# mSD-Shield-Mega_v11.net
KiCad netlist of a schematic drawn in EAGLE
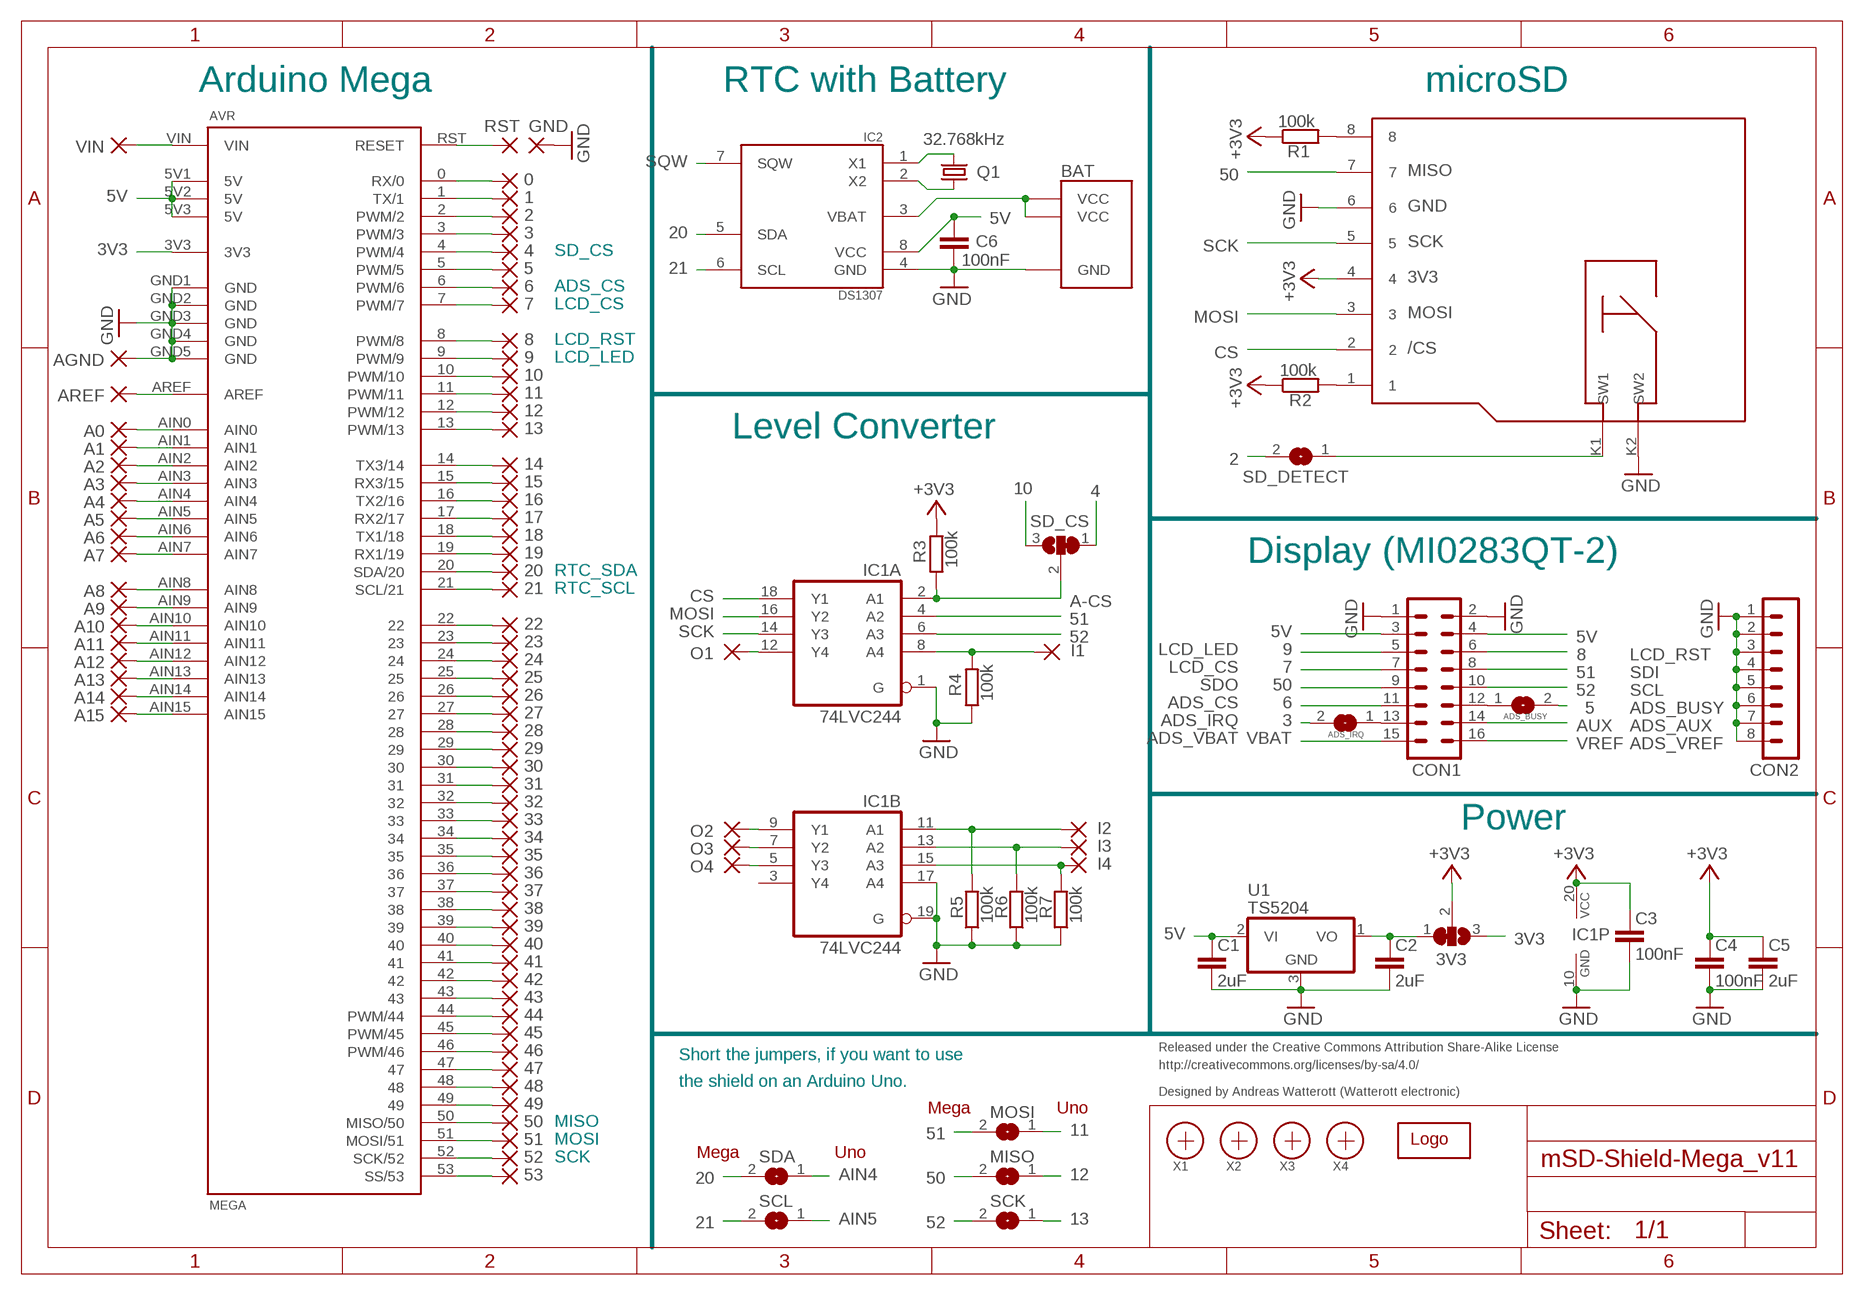
[diagram p0: schematic, sheet 1]

(export (version "E")
  (design (tool "Eeschema 10.0.6"))
  (components
    (comp (ref "0")
      (value "1,6/0,8")
      (footprint "eagle-import:1,6_0,8")
      (libsource (lib "eagle-import") (part "1,6/0,8"))
    )
    (comp (ref "1")
      (value "1,6/0,8")
      (footprint "eagle-import:1,6_0,8")
      (libsource (lib "eagle-import") (part "1,6/0,8"))
    )
    (comp (ref "2")
      (value "1,6/0,8")
      (footprint "eagle-import:1,6_0,8")
      (libsource (lib "eagle-import") (part "1,6/0,8"))
    )
    (comp (ref "3")
      (value "1,6/0,8")
      (footprint "eagle-import:1,6_0,8")
      (libsource (lib "eagle-import") (part "1,6/0,8"))
    )
    (comp (ref "3V3")
      (value "SJ2W")
      (footprint "eagle-import:SJ_2")
      (libsource (lib "eagle-import") (part "SJ2W"))
    )
    (comp (ref "4")
      (value "1,6/0,8")
      (footprint "eagle-import:1,6_0,8")
      (libsource (lib "eagle-import") (part "1,6/0,8"))
    )
    (comp (ref "5")
      (value "1,6/0,8")
      (footprint "eagle-import:1,6_0,8")
      (libsource (lib "eagle-import") (part "1,6/0,8"))
    )
    (comp (ref "6")
      (value "1,6/0,8")
      (footprint "eagle-import:1,6_0,8")
      (libsource (lib "eagle-import") (part "1,6/0,8"))
    )
    (comp (ref "7")
      (value "1,6/0,8")
      (footprint "eagle-import:1,6_0,8")
      (libsource (lib "eagle-import") (part "1,6/0,8"))
    )
    (comp (ref "8")
      (value "1,6/0,8")
      (footprint "eagle-import:1,6_0,8")
      (libsource (lib "eagle-import") (part "1,6/0,8"))
    )
    (comp (ref "9")
      (value "1,6/0,8")
      (footprint "eagle-import:1,6_0,8")
      (libsource (lib "eagle-import") (part "1,6/0,8"))
    )
    (comp (ref "10")
      (value "1,6/0,8")
      (footprint "eagle-import:1,6_0,8")
      (libsource (lib "eagle-import") (part "1,6/0,8"))
    )
    (comp (ref "11")
      (value "1,6/0,8")
      (footprint "eagle-import:1,6_0,8")
      (libsource (lib "eagle-import") (part "1,6/0,8"))
    )
    (comp (ref "12")
      (value "1,6/0,8")
      (footprint "eagle-import:1,6_0,8")
      (libsource (lib "eagle-import") (part "1,6/0,8"))
    )
    (comp (ref "13")
      (value "1,6/0,8")
      (footprint "eagle-import:1,6_0,8")
      (libsource (lib "eagle-import") (part "1,6/0,8"))
    )
    (comp (ref "14")
      (value "1,6/0,8")
      (footprint "eagle-import:1,6_0,8")
      (libsource (lib "eagle-import") (part "1,6/0,8"))
    )
    (comp (ref "15")
      (value "1,6/0,8")
      (footprint "eagle-import:1,6_0,8")
      (libsource (lib "eagle-import") (part "1,6/0,8"))
    )
    (comp (ref "16")
      (value "1,6/0,8")
      (footprint "eagle-import:1,6_0,8")
      (libsource (lib "eagle-import") (part "1,6/0,8"))
    )
    (comp (ref "17")
      (value "1,6/0,8")
      (footprint "eagle-import:1,6_0,8")
      (libsource (lib "eagle-import") (part "1,6/0,8"))
    )
    (comp (ref "18")
      (value "1,6/0,8")
      (footprint "eagle-import:1,6_0,8")
      (libsource (lib "eagle-import") (part "1,6/0,8"))
    )
    (comp (ref "19")
      (value "1,6/0,8")
      (footprint "eagle-import:1,6_0,8")
      (libsource (lib "eagle-import") (part "1,6/0,8"))
    )
    (comp (ref "20")
      (value "1,6/0,8")
      (footprint "eagle-import:1,6_0,8")
      (libsource (lib "eagle-import") (part "1,6/0,8"))
    )
    (comp (ref "21")
      (value "1,6/0,8")
      (footprint "eagle-import:1,6_0,8")
      (libsource (lib "eagle-import") (part "1,6/0,8"))
    )
    (comp (ref "22")
      (value "1,6/0,8")
      (footprint "eagle-import:1,6_0,8")
      (libsource (lib "eagle-import") (part "1,6/0,8"))
    )
    (comp (ref "23")
      (value "1,6/0,8")
      (footprint "eagle-import:1,6_0,8")
      (libsource (lib "eagle-import") (part "1,6/0,8"))
    )
    (comp (ref "24")
      (value "1,6/0,8")
      (footprint "eagle-import:1,6_0,8")
      (libsource (lib "eagle-import") (part "1,6/0,8"))
    )
    (comp (ref "25")
      (value "1,6/0,8")
      (footprint "eagle-import:1,6_0,8")
      (libsource (lib "eagle-import") (part "1,6/0,8"))
    )
    (comp (ref "26")
      (value "1,6/0,8")
      (footprint "eagle-import:1,6_0,8")
      (libsource (lib "eagle-import") (part "1,6/0,8"))
    )
    (comp (ref "27")
      (value "1,6/0,8")
      (footprint "eagle-import:1,6_0,8")
      (libsource (lib "eagle-import") (part "1,6/0,8"))
    )
    (comp (ref "28")
      (value "1,6/0,8")
      (footprint "eagle-import:1,6_0,8")
      (libsource (lib "eagle-import") (part "1,6/0,8"))
    )
    (comp (ref "29")
      (value "1,6/0,8")
      (footprint "eagle-import:1,6_0,8")
      (libsource (lib "eagle-import") (part "1,6/0,8"))
    )
    (comp (ref "30")
      (value "1,6/0,8")
      (footprint "eagle-import:1,6_0,8")
      (libsource (lib "eagle-import") (part "1,6/0,8"))
    )
    (comp (ref "31")
      (value "1,6/0,8")
      (footprint "eagle-import:1,6_0,8")
      (libsource (lib "eagle-import") (part "1,6/0,8"))
    )
    (comp (ref "32")
      (value "1,6/0,8")
      (footprint "eagle-import:1,6_0,8")
      (libsource (lib "eagle-import") (part "1,6/0,8"))
    )
    (comp (ref "33")
      (value "1,6/0,8")
      (footprint "eagle-import:1,6_0,8")
      (libsource (lib "eagle-import") (part "1,6/0,8"))
    )
    (comp (ref "34")
      (value "1,6/0,8")
      (footprint "eagle-import:1,6_0,8")
      (libsource (lib "eagle-import") (part "1,6/0,8"))
    )
    (comp (ref "35")
      (value "1,6/0,8")
      (footprint "eagle-import:1,6_0,8")
      (libsource (lib "eagle-import") (part "1,6/0,8"))
    )
    (comp (ref "36")
      (value "1,6/0,8")
      (footprint "eagle-import:1,6_0,8")
      (libsource (lib "eagle-import") (part "1,6/0,8"))
    )
    (comp (ref "37")
      (value "1,6/0,8")
      (footprint "eagle-import:1,6_0,8")
      (libsource (lib "eagle-import") (part "1,6/0,8"))
    )
    (comp (ref "38")
      (value "1,6/0,8")
      (footprint "eagle-import:1,6_0,8")
      (libsource (lib "eagle-import") (part "1,6/0,8"))
    )
    (comp (ref "39")
      (value "1,6/0,8")
      (footprint "eagle-import:1,6_0,8")
      (libsource (lib "eagle-import") (part "1,6/0,8"))
    )
    (comp (ref "40")
      (value "1,6/0,8")
      (footprint "eagle-import:1,6_0,8")
      (libsource (lib "eagle-import") (part "1,6/0,8"))
    )
    (comp (ref "41")
      (value "1,6/0,8")
      (footprint "eagle-import:1,6_0,8")
      (libsource (lib "eagle-import") (part "1,6/0,8"))
    )
    (comp (ref "42")
      (value "1,6/0,8")
      (footprint "eagle-import:1,6_0,8")
      (libsource (lib "eagle-import") (part "1,6/0,8"))
    )
    (comp (ref "43")
      (value "1,6/0,8")
      (footprint "eagle-import:1,6_0,8")
      (libsource (lib "eagle-import") (part "1,6/0,8"))
    )
    (comp (ref "44")
      (value "1,6/0,8")
      (footprint "eagle-import:1,6_0,8")
      (libsource (lib "eagle-import") (part "1,6/0,8"))
    )
    (comp (ref "45")
      (value "1,6/0,8")
      (footprint "eagle-import:1,6_0,8")
      (libsource (lib "eagle-import") (part "1,6/0,8"))
    )
    (comp (ref "46")
      (value "1,6/0,8")
      (footprint "eagle-import:1,6_0,8")
      (libsource (lib "eagle-import") (part "1,6/0,8"))
    )
    (comp (ref "47")
      (value "1,6/0,8")
      (footprint "eagle-import:1,6_0,8")
      (libsource (lib "eagle-import") (part "1,6/0,8"))
    )
    (comp (ref "48")
      (value "1,6/0,8")
      (footprint "eagle-import:1,6_0,8")
      (libsource (lib "eagle-import") (part "1,6/0,8"))
    )
    (comp (ref "49")
      (value "1,6/0,8")
      (footprint "eagle-import:1,6_0,8")
      (libsource (lib "eagle-import") (part "1,6/0,8"))
    )
    (comp (ref "50")
      (value "1,6/0,8")
      (footprint "eagle-import:1,6_0,8")
      (libsource (lib "eagle-import") (part "1,6/0,8"))
    )
    (comp (ref "51")
      (value "1,6/0,8")
      (footprint "eagle-import:1,6_0,8")
      (libsource (lib "eagle-import") (part "1,6/0,8"))
    )
    (comp (ref "52")
      (value "1,6/0,8")
      (footprint "eagle-import:1,6_0,8")
      (libsource (lib "eagle-import") (part "1,6/0,8"))
    )
    (comp (ref "53")
      (value "1,6/0,8")
      (footprint "eagle-import:1,6_0,8")
      (libsource (lib "eagle-import") (part "1,6/0,8"))
    )
    (comp (ref "A0")
      (value "1,6/0,8")
      (footprint "eagle-import:1,6_0,8")
      (libsource (lib "eagle-import") (part "1,6/0,8"))
    )
    (comp (ref "A1")
      (value "1,6/0,8")
      (footprint "eagle-import:1,6_0,8")
      (libsource (lib "eagle-import") (part "1,6/0,8"))
    )
    (comp (ref "A2")
      (value "1,6/0,8")
      (footprint "eagle-import:1,6_0,8")
      (libsource (lib "eagle-import") (part "1,6/0,8"))
    )
    (comp (ref "A3")
      (value "1,6/0,8")
      (footprint "eagle-import:1,6_0,8")
      (libsource (lib "eagle-import") (part "1,6/0,8"))
    )
    (comp (ref "A4")
      (value "1,6/0,8")
      (footprint "eagle-import:1,6_0,8")
      (libsource (lib "eagle-import") (part "1,6/0,8"))
    )
    (comp (ref "A5")
      (value "1,6/0,8")
      (footprint "eagle-import:1,6_0,8")
      (libsource (lib "eagle-import") (part "1,6/0,8"))
    )
    (comp (ref "A6")
      (value "1,6/0,8")
      (footprint "eagle-import:1,6_0,8")
      (libsource (lib "eagle-import") (part "1,6/0,8"))
    )
    (comp (ref "A7")
      (value "1,6/0,8")
      (footprint "eagle-import:1,6_0,8")
      (libsource (lib "eagle-import") (part "1,6/0,8"))
    )
    (comp (ref "A8")
      (value "1,6/0,8")
      (footprint "eagle-import:1,6_0,8")
      (libsource (lib "eagle-import") (part "1,6/0,8"))
    )
    (comp (ref "A9")
      (value "1,6/0,8")
      (footprint "eagle-import:1,6_0,8")
      (libsource (lib "eagle-import") (part "1,6/0,8"))
    )
    (comp (ref "A10")
      (value "1,6/0,8")
      (footprint "eagle-import:1,6_0,8")
      (libsource (lib "eagle-import") (part "1,6/0,8"))
    )
    (comp (ref "A11")
      (value "1,6/0,8")
      (footprint "eagle-import:1,6_0,8")
      (libsource (lib "eagle-import") (part "1,6/0,8"))
    )
    (comp (ref "A12")
      (value "1,6/0,8")
      (footprint "eagle-import:1,6_0,8")
      (libsource (lib "eagle-import") (part "1,6/0,8"))
    )
    (comp (ref "A13")
      (value "1,6/0,8")
      (footprint "eagle-import:1,6_0,8")
      (libsource (lib "eagle-import") (part "1,6/0,8"))
    )
    (comp (ref "A14")
      (value "1,6/0,8")
      (footprint "eagle-import:1,6_0,8")
      (libsource (lib "eagle-import") (part "1,6/0,8"))
    )
    (comp (ref "A15")
      (value "1,6/0,8")
      (footprint "eagle-import:1,6_0,8")
      (libsource (lib "eagle-import") (part "1,6/0,8"))
    )
    (comp (ref "ADS_BUSY")
      (value "SJ")
      (footprint "eagle-import:SJ")
      (libsource (lib "eagle-import") (part "SJ"))
    )
    (comp (ref "ADS_IRQ")
      (value "SJ")
      (footprint "eagle-import:SJ")
      (libsource (lib "eagle-import") (part "SJ"))
    )
    (comp (ref "AGND")
      (value "1,6/0,8")
      (footprint "eagle-import:1,6_0,8")
      (libsource (lib "eagle-import") (part "1,6/0,8"))
    )
    (comp (ref "AREF")
      (value "1,6/0,8")
      (footprint "eagle-import:1,6_0,8")
      (libsource (lib "eagle-import") (part "1,6/0,8"))
    )
    (comp (ref "AVR")
      (value "MEGA")
      (footprint "eagle-import:MEGA")
      (libsource (lib "eagle-import") (part "MEGA"))
    )
    (comp (ref "BAT")
      (value "CR2032")
      (footprint "eagle-import:KC3002S")
      (libsource (lib "eagle-import") (part "KC3002S"))
    )
    (comp (ref "C1")
      (value "2uF")
      (footprint "eagle-import:C0805")
      (libsource (lib "eagle-import") (part "C-EUC0805"))
    )
    (comp (ref "C2")
      (value "2uF")
      (footprint "eagle-import:C0805")
      (libsource (lib "eagle-import") (part "C-EUC0805"))
    )
    (comp (ref "C3")
      (value "100nF")
      (footprint "eagle-import:C0603")
      (libsource (lib "eagle-import") (part "C-EUC0603"))
    )
    (comp (ref "C4")
      (value "100nF")
      (footprint "eagle-import:C0603")
      (libsource (lib "eagle-import") (part "C-EUC0603"))
    )
    (comp (ref "C5")
      (value "2uF")
      (footprint "eagle-import:C0603")
      (libsource (lib "eagle-import") (part "C-EUC0603"))
    )
    (comp (ref "C6")
      (value "100nF")
      (footprint "eagle-import:C0603")
      (libsource (lib "eagle-import") (part "C-EUC0603"))
    )
    (comp (ref "CON1")
      (value "MA08-2")
      (footprint "eagle-import:MA08-2")
      (libsource (lib "eagle-import") (part "MA08-2"))
    )
    (comp (ref "CON2")
      (value "MA08-1")
      (footprint "eagle-import:MA08-1")
      (libsource (lib "eagle-import") (part "MA08-1"))
    )
    (comp (ref "GND")
      (value "SMD2")
      (footprint "eagle-import:SMD1,27-2,54")
      (libsource (lib "eagle-import") (part "SMD2"))
    )
    (comp (ref "I1")
      (value "SMD2")
      (footprint "eagle-import:SMD1,27-2,54")
      (libsource (lib "eagle-import") (part "SMD2"))
    )
    (comp (ref "I2")
      (value "SMD2")
      (footprint "eagle-import:SMD1,27-2,54")
      (libsource (lib "eagle-import") (part "SMD2"))
    )
    (comp (ref "I3")
      (value "SMD2")
      (footprint "eagle-import:SMD1,27-2,54")
      (libsource (lib "eagle-import") (part "SMD2"))
    )
    (comp (ref "I4")
      (value "SMD2")
      (footprint "eagle-import:SMD1,27-2,54")
      (libsource (lib "eagle-import") (part "SMD2"))
    )
    (comp (ref "IC1")
      (value "74LVC244")
      (footprint "eagle-import:SO20W")
      (libsource (lib "eagle-import") (part "74244DWHC"))
    )
    (comp (ref "IC2")
      (value "DS1307")
      (footprint "eagle-import:SO8")
      (libsource (lib "eagle-import") (part "DS1307"))
    )
    (comp (ref "MISO")
      (value "SJ")
      (footprint "eagle-import:SJ")
      (libsource (lib "eagle-import") (part "SJ"))
    )
    (comp (ref "MOSI")
      (value "SJ")
      (footprint "eagle-import:SJ")
      (libsource (lib "eagle-import") (part "SJ"))
    )
    (comp (ref "O1")
      (value "SMD2")
      (footprint "eagle-import:SMD1,27-2,54")
      (libsource (lib "eagle-import") (part "SMD2"))
    )
    (comp (ref "O2")
      (value "SMD2")
      (footprint "eagle-import:SMD1,27-2,54")
      (libsource (lib "eagle-import") (part "SMD2"))
    )
    (comp (ref "O3")
      (value "SMD2")
      (footprint "eagle-import:SMD1,27-2,54")
      (libsource (lib "eagle-import") (part "SMD2"))
    )
    (comp (ref "O4")
      (value "SMD2")
      (footprint "eagle-import:SMD1,27-2,54")
      (libsource (lib "eagle-import") (part "SMD2"))
    )
    (comp (ref "Q1")
      (value "32.768kHz")
      (footprint "eagle-import:TC26V")
      (libsource (lib "eagle-import") (part "CRYSTALTC26V"))
    )
    (comp (ref "R1")
      (value "100k")
      (footprint "eagle-import:R0603")
      (libsource (lib "eagle-import") (part "R-EU_R0603"))
    )
    (comp (ref "R2")
      (value "100k")
      (footprint "eagle-import:R0603")
      (libsource (lib "eagle-import") (part "R-EU_R0603"))
    )
    (comp (ref "R3")
      (value "100k")
      (footprint "eagle-import:R0603")
      (libsource (lib "eagle-import") (part "R-EU_R0603"))
    )
    (comp (ref "R4")
      (value "100k")
      (footprint "eagle-import:R0603")
      (libsource (lib "eagle-import") (part "R-EU_R0603"))
    )
    (comp (ref "R5")
      (value "100k")
      (footprint "eagle-import:R0603")
      (libsource (lib "eagle-import") (part "R-EU_R0603"))
    )
    (comp (ref "R6")
      (value "100k")
      (footprint "eagle-import:R0603")
      (libsource (lib "eagle-import") (part "R-EU_R0603"))
    )
    (comp (ref "R7")
      (value "100k")
      (footprint "eagle-import:R0603")
      (libsource (lib "eagle-import") (part "R-EU_R0603"))
    )
    (comp (ref "RST")
      (value "SMD2")
      (footprint "eagle-import:SMD1,27-2,54")
      (libsource (lib "eagle-import") (part "SMD2"))
    )
    (comp (ref "SCK") (value "SJ") (footprint "eagle-import:SJ") (libsource (lib "eagle-import") (part "SJ")))
    (comp (ref "SCL") (value "SJ") (footprint "eagle-import:SJ") (libsource (lib "eagle-import") (part "SJ")))
    (comp (ref "SDA") (value "SJ") (footprint "eagle-import:SJ") (libsource (lib "eagle-import") (part "SJ")))
    (comp (ref "SD_CS")
      (value "SJ2W")
      (footprint "eagle-import:SJ_2")
      (libsource (lib "eagle-import") (part "SJ2W"))
    )
    (comp (ref "SD_DETECT")
      (value "SJ")
      (footprint "eagle-import:SJ")
      (libsource (lib "eagle-import") (part "SJ"))
    )
    (comp (ref "U$1")
      (value "WE-LOGO")
      (footprint "eagle-import:WE-LOGO")
      (libsource (lib "eagle-import") (part "WE-LOGO"))
    )
    (comp (ref "U1")
      (value "TS5204")
      (footprint "eagle-import:SOT23")
      (libsource (lib "eagle-import") (part "TS5204"))
    )
    (comp (ref "VIN")
      (value "1,6/0,8")
      (footprint "eagle-import:1,6_0,8")
      (libsource (lib "eagle-import") (part "1,6/0,8"))
    )
    (comp (ref "X1")
      (value "PASSER")
      (footprint "eagle-import:PASSER")
      (libsource (lib "eagle-import") (part "PASSER"))
    )
    (comp (ref "X2")
      (value "PASSER")
      (footprint "eagle-import:PASSER")
      (libsource (lib "eagle-import") (part "PASSER"))
    )
    (comp (ref "X3")
      (value "PASSER")
      (footprint "eagle-import:PASSER")
      (libsource (lib "eagle-import") (part "PASSER"))
    )
    (comp (ref "X4")
      (value "PASSER")
      (footprint "eagle-import:PASSER")
      (libsource (lib "eagle-import") (part "PASSER"))
    )
    (comp (ref "X5")
      (value "MICRO-SD")
      (footprint "eagle-import:MICRO-SD")
      (libsource (lib "eagle-import") (part "MICRO-SD"))
    )
  )
  (nets
    (net (code "1") (name "+3V3") (class "Default")
      (node (ref "3V3") (pin "2") (pinfunction "2_2") (pintype "passive"))
      (node (ref "C3") (pin "1") (pinfunction "1_1") (pintype "passive"))
      (node (ref "C4") (pin "1") (pinfunction "1_1") (pintype "passive"))
      (node (ref "C5") (pin "1") (pinfunction "1_1") (pintype "passive"))
      (node (ref "IC1") (pin "20") (pinfunction "VCC_20") (pintype "power_in"))
      (node (ref "R1") (pin "1") (pinfunction "1_1") (pintype "passive"))
      (node (ref "R2") (pin "1") (pinfunction "1_1") (pintype "passive"))
      (node (ref "R3") (pin "2") (pinfunction "2_2") (pintype "passive"))
      (node (ref "X5") (pin "4") (pinfunction "4_4") (pintype "bidirectional"))
    )
    (net (code "2") (name "/2") (class "Default")
      (node (ref "2") (pin "1") (pinfunction "P_1") (pintype "passive"))
      (node (ref "AVR") (pin "2") (pinfunction "PWM/2_2") (pintype "bidirectional"))
      (node (ref "SD_DETECT") (pin "2") (pinfunction "2_2") (pintype "passive"))
    )
    (net (code "3") (name "/3") (class "Default")
      (node (ref "3") (pin "1") (pinfunction "P_1") (pintype "passive"))
      (node (ref "ADS_IRQ") (pin "2") (pinfunction "2_2") (pintype "passive"))
      (node (ref "AVR") (pin "3") (pinfunction "PWM/3_3") (pintype "bidirectional"))
    )
    (net (code "4") (name "/3V3") (class "Default")
      (node (ref "3V3") (pin "3") (pinfunction "3_3") (pintype "passive"))
      (node (ref "AVR") (pin "3V3") (pinfunction "3V3_3V3") (pintype "power_in"))
    )
    (net (code "5") (name "/4") (class "Default")
      (node (ref "4") (pin "1") (pinfunction "P_1") (pintype "passive"))
      (node (ref "AVR") (pin "4") (pinfunction "PWM/4_4") (pintype "bidirectional"))
      (node (ref "SD_CS") (pin "1") (pinfunction "1_1") (pintype "passive"))
    )
    (net (code "6") (name "/5") (class "Default")
      (node (ref "5") (pin "1") (pinfunction "P_1") (pintype "passive"))
      (node (ref "ADS_BUSY") (pin "2") (pinfunction "2_2") (pintype "passive"))
      (node (ref "AVR") (pin "5") (pinfunction "PWM/5_5") (pintype "bidirectional"))
    )
    (net (code "7") (name "/5V") (class "Default")
      (node (ref "AVR") (pin "5V1") (pinfunction "5V_5V1") (pintype "power_in"))
      (node (ref "AVR") (pin "5V2") (pinfunction "5V_5V2") (pintype "power_in"))
      (node (ref "AVR") (pin "5V3") (pinfunction "5V_5V3") (pintype "power_in"))
      (node (ref "C1") (pin "1") (pinfunction "1_1") (pintype "passive"))
      (node (ref "C6") (pin "2") (pinfunction "2_2") (pintype "passive"))
      (node (ref "CON1") (pin "3") (pinfunction "3_3") (pintype "passive"))
      (node (ref "CON1") (pin "4") (pinfunction "4_4") (pintype "passive"))
      (node (ref "IC2") (pin "8") (pinfunction "VCC_8") (pintype "power_in"))
      (node (ref "U1") (pin "2") (pinfunction "VI_2") (pintype "input"))
    )
    (net (code "8") (name "/6") (class "Default")
      (node (ref "6") (pin "1") (pinfunction "P_1") (pintype "passive"))
      (node (ref "AVR") (pin "6") (pinfunction "PWM/6_6") (pintype "bidirectional"))
      (node (ref "CON1") (pin "11") (pinfunction "11_11") (pintype "passive"))
    )
    (net (code "9") (name "/7") (class "Default")
      (node (ref "7") (pin "1") (pinfunction "P_1") (pintype "passive"))
      (node (ref "AVR") (pin "7") (pinfunction "PWM/7_7") (pintype "bidirectional"))
      (node (ref "CON1") (pin "7") (pinfunction "7_7") (pintype "passive"))
    )
    (net (code "10") (name "/8") (class "Default")
      (node (ref "8") (pin "1") (pinfunction "P_1") (pintype "passive"))
      (node (ref "AVR") (pin "8") (pinfunction "PWM/8_8") (pintype "bidirectional"))
      (node (ref "CON1") (pin "6") (pinfunction "6_6") (pintype "passive"))
    )
    (net (code "11") (name "/9") (class "Default")
      (node (ref "9") (pin "1") (pinfunction "P_1") (pintype "passive"))
      (node (ref "AVR") (pin "9") (pinfunction "PWM/9_9") (pintype "bidirectional"))
      (node (ref "CON1") (pin "5") (pinfunction "5_5") (pintype "passive"))
    )
    (net (code "12") (name "/10") (class "Default")
      (node (ref "10") (pin "1") (pinfunction "P_1") (pintype "passive"))
      (node (ref "AVR") (pin "10") (pinfunction "PWM/10_10") (pintype "bidirectional"))
      (node (ref "SD_CS") (pin "3") (pinfunction "3_3") (pintype "passive"))
    )
    (net (code "13") (name "/11") (class "Default")
      (node (ref "11") (pin "1") (pinfunction "P_1") (pintype "passive"))
      (node (ref "AVR") (pin "11") (pinfunction "PWM/11_11") (pintype "bidirectional"))
      (node (ref "MOSI") (pin "1") (pinfunction "1_1") (pintype "passive"))
    )
    (net (code "14") (name "/12") (class "Default")
      (node (ref "12") (pin "1") (pinfunction "P_1") (pintype "passive"))
      (node (ref "AVR") (pin "12") (pinfunction "PWM/12_12") (pintype "bidirectional"))
      (node (ref "MISO") (pin "1") (pinfunction "1_1") (pintype "passive"))
    )
    (net (code "15") (name "/13") (class "Default")
      (node (ref "13") (pin "1") (pinfunction "P_1") (pintype "passive"))
      (node (ref "AVR") (pin "13") (pinfunction "PWM/13_13") (pintype "bidirectional"))
      (node (ref "SCK") (pin "1") (pinfunction "1_1") (pintype "passive"))
    )
    (net (code "16") (name "/20") (class "Default")
      (node (ref "20") (pin "1") (pinfunction "P_1") (pintype "passive"))
      (node (ref "AVR") (pin "20") (pinfunction "SDA/20_20") (pintype "bidirectional"))
      (node (ref "IC2") (pin "5") (pinfunction "SDA_5") (pintype "bidirectional"))
      (node (ref "SDA") (pin "2") (pinfunction "2_2") (pintype "passive"))
    )
    (net (code "17") (name "/21") (class "Default")
      (node (ref "21") (pin "1") (pinfunction "P_1") (pintype "passive"))
      (node (ref "AVR") (pin "21") (pinfunction "SCL/21_21") (pintype "bidirectional"))
      (node (ref "IC2") (pin "6") (pinfunction "SCL_6") (pintype "bidirectional"))
      (node (ref "SCL") (pin "2") (pinfunction "2_2") (pintype "passive"))
    )
    (net (code "18") (name "/50") (class "Default")
      (node (ref "50") (pin "1") (pinfunction "P_1") (pintype "passive"))
      (node (ref "AVR") (pin "50") (pinfunction "MISO/50_50") (pintype "bidirectional"))
      (node (ref "CON1") (pin "9") (pinfunction "9_9") (pintype "passive"))
      (node (ref "MISO") (pin "2") (pinfunction "2_2") (pintype "passive"))
      (node (ref "X5") (pin "7") (pinfunction "7_7") (pintype "bidirectional"))
    )
    (net (code "19") (name "/51") (class "Default")
      (node (ref "51") (pin "1") (pinfunction "P_1") (pintype "passive"))
      (node (ref "AVR") (pin "51") (pinfunction "MOSI/51_51") (pintype "bidirectional"))
      (node (ref "CON1") (pin "8") (pinfunction "8_8") (pintype "passive"))
      (node (ref "IC1") (pin "4") (pinfunction "A2_4") (pintype "input"))
      (node (ref "MOSI") (pin "2") (pinfunction "2_2") (pintype "passive"))
    )
    (net (code "20") (name "/52") (class "Default")
      (node (ref "52") (pin "1") (pinfunction "P_1") (pintype "passive"))
      (node (ref "AVR") (pin "52") (pinfunction "SCK/52_52") (pintype "bidirectional"))
      (node (ref "CON1") (pin "10") (pinfunction "10_10") (pintype "passive"))
      (node (ref "IC1") (pin "6") (pinfunction "A3_6") (pintype "input"))
      (node (ref "SCK") (pin "2") (pinfunction "2_2") (pintype "passive"))
    )
    (net (code "21") (name "/A-CS") (class "Default")
      (node (ref "IC1") (pin "2") (pinfunction "A1_2") (pintype "input"))
      (node (ref "R3") (pin "1") (pinfunction "1_1") (pintype "passive"))
      (node (ref "SD_CS") (pin "2") (pinfunction "2_2") (pintype "passive"))
    )
    (net (code "22") (name "/AIN4") (class "Default")
      (node (ref "A4") (pin "1") (pinfunction "P_1") (pintype "passive"))
      (node (ref "AVR") (pin "AIN4") (pinfunction "AIN4_AIN4") (pintype "bidirectional"))
      (node (ref "SDA") (pin "1") (pinfunction "1_1") (pintype "passive"))
    )
    (net (code "23") (name "/AIN5") (class "Default")
      (node (ref "A5") (pin "1") (pinfunction "P_1") (pintype "passive"))
      (node (ref "AVR") (pin "AIN5") (pinfunction "AIN5_AIN5") (pintype "bidirectional"))
      (node (ref "SCL") (pin "1") (pinfunction "1_1") (pintype "passive"))
    )
    (net (code "24") (name "/AUX") (class "Default")
      (node (ref "CON1") (pin "14") (pinfunction "14_14") (pintype "passive"))
    )
    (net (code "25") (name "/CS") (class "Default")
      (node (ref "IC1") (pin "18") (pinfunction "Y1_18") (pintype "tri_state"))
      (node (ref "X5") (pin "2") (pinfunction "2_2") (pintype "bidirectional"))
    )
    (net (code "26") (name "/MOSI") (class "Default")
      (node (ref "IC1") (pin "16") (pinfunction "Y2_16") (pintype "tri_state"))
      (node (ref "X5") (pin "3") (pinfunction "3_3") (pintype "bidirectional"))
    )
    (net (code "27") (name "/SCK") (class "Default")
      (node (ref "IC1") (pin "14") (pinfunction "Y3_14") (pintype "tri_state"))
      (node (ref "X5") (pin "5") (pinfunction "5_5") (pintype "bidirectional"))
    )
    (net (code "28") (name "/SQW") (class "Default")
      (node (ref "IC2") (pin "7") (pinfunction "SQW_7") (pintype "bidirectional"))
    )
    (net (code "29") (name "/VBAT") (class "Default")
      (node (ref "CON1") (pin "15") (pinfunction "15_15") (pintype "passive"))
    )
    (net (code "30") (name "/VREF") (class "Default")
      (node (ref "CON1") (pin "16") (pinfunction "16_16") (pintype "passive"))
    )
    (net (code "31") (name "GND") (class "Default")
      (node (ref "AGND") (pin "1") (pinfunction "P_1") (pintype "passive"))
      (node (ref "AVR") (pin "GND1") (pinfunction "GND_GND1") (pintype "power_in"))
      (node (ref "AVR") (pin "GND2") (pinfunction "GND_GND2") (pintype "power_in"))
      (node (ref "AVR") (pin "GND3") (pinfunction "GND_GND3") (pintype "power_in"))
      (node (ref "AVR") (pin "GND4") (pinfunction "GND_GND4") (pintype "power_in"))
      (node (ref "AVR") (pin "GND5") (pinfunction "GND_GND5") (pintype "power_in"))
      (node (ref "BAT") (pin "GND") (pinfunction "GND_GND") (pintype "power_in"))
      (node (ref "C1") (pin "2") (pinfunction "2_2") (pintype "passive"))
      (node (ref "C2") (pin "2") (pinfunction "2_2") (pintype "passive"))
      (node (ref "C3") (pin "2") (pinfunction "2_2") (pintype "passive"))
      (node (ref "C4") (pin "2") (pinfunction "2_2") (pintype "passive"))
      (node (ref "C5") (pin "2") (pinfunction "2_2") (pintype "passive"))
      (node (ref "C6") (pin "1") (pinfunction "1_1") (pintype "passive"))
      (node (ref "CON1") (pin "1") (pinfunction "1_1") (pintype "passive"))
      (node (ref "CON1") (pin "2") (pinfunction "2_2") (pintype "passive"))
      (node (ref "CON2") (pin "1") (pinfunction "1_1") (pintype "passive"))
      (node (ref "CON2") (pin "2") (pinfunction "2_2") (pintype "passive"))
      (node (ref "CON2") (pin "3") (pinfunction "3_3") (pintype "passive"))
      (node (ref "CON2") (pin "4") (pinfunction "4_4") (pintype "passive"))
      (node (ref "CON2") (pin "5") (pinfunction "5_5") (pintype "passive"))
      (node (ref "CON2") (pin "6") (pinfunction "6_6") (pintype "passive"))
      (node (ref "CON2") (pin "7") (pinfunction "7_7") (pintype "passive"))
      (node (ref "CON2") (pin "8") (pinfunction "8_8") (pintype "passive"))
      (node (ref "GND") (pin "1") (pinfunction "P_1") (pintype "passive"))
      (node (ref "IC1") (pin "1") (pinfunction "G_1") (pintype "input"))
      (node (ref "IC1") (pin "10") (pinfunction "GND_10") (pintype "power_in"))
      (node (ref "IC1") (pin "17") (pinfunction "A4_17") (pintype "input"))
      (node (ref "IC1") (pin "19") (pinfunction "G_19") (pintype "input"))
      (node (ref "IC2") (pin "4") (pinfunction "GND_4") (pintype "power_in"))
      (node (ref "R4") (pin "1") (pinfunction "1_1") (pintype "passive"))
      (node (ref "R5") (pin "1") (pinfunction "1_1") (pintype "passive"))
      (node (ref "R6") (pin "1") (pinfunction "1_1") (pintype "passive"))
      (node (ref "R7") (pin "1") (pinfunction "1_1") (pintype "passive"))
      (node (ref "U1") (pin "3") (pinfunction "GND_3") (pintype "passive"))
      (node (ref "X5") (pin "6") (pinfunction "6_6") (pintype "bidirectional"))
      (node (ref "X5") (pin "K2") (pinfunction "SW2_K2") (pintype "bidirectional"))
    )
    (net (code "32") (name "Net-(0-P)") (class "Default")
      (node (ref "0") (pin "1") (pinfunction "P_1") (pintype "passive"))
      (node (ref "AVR") (pin "0") (pinfunction "RX/0_0") (pintype "bidirectional"))
    )
    (net (code "33") (name "Net-(1-P)") (class "Default")
      (node (ref "1") (pin "1") (pinfunction "P_1") (pintype "passive"))
      (node (ref "AVR") (pin "1") (pinfunction "TX/1_1") (pintype "bidirectional"))
    )
    (net (code "34") (name "Net-(14-P)") (class "Default")
      (node (ref "14") (pin "1") (pinfunction "P_1") (pintype "passive"))
      (node (ref "AVR") (pin "14") (pinfunction "TX3/14_14") (pintype "bidirectional"))
    )
    (net (code "35") (name "Net-(15-P)") (class "Default")
      (node (ref "15") (pin "1") (pinfunction "P_1") (pintype "passive"))
      (node (ref "AVR") (pin "15") (pinfunction "RX3/15_15") (pintype "bidirectional"))
    )
    (net (code "36") (name "Net-(16-P)") (class "Default")
      (node (ref "16") (pin "1") (pinfunction "P_1") (pintype "passive"))
      (node (ref "AVR") (pin "16") (pinfunction "TX2/16_16") (pintype "bidirectional"))
    )
    (net (code "37") (name "Net-(17-P)") (class "Default")
      (node (ref "17") (pin "1") (pinfunction "P_1") (pintype "passive"))
      (node (ref "AVR") (pin "17") (pinfunction "RX2/17_17") (pintype "bidirectional"))
    )
    (net (code "38") (name "Net-(18-P)") (class "Default")
      (node (ref "18") (pin "1") (pinfunction "P_1") (pintype "passive"))
      (node (ref "AVR") (pin "18") (pinfunction "TX1/18_18") (pintype "bidirectional"))
    )
    (net (code "39") (name "Net-(19-P)") (class "Default")
      (node (ref "19") (pin "1") (pinfunction "P_1") (pintype "passive"))
      (node (ref "AVR") (pin "19") (pinfunction "RX1/19_19") (pintype "bidirectional"))
    )
    (net (code "40") (name "Net-(22-P)") (class "Default")
      (node (ref "22") (pin "1") (pinfunction "P_1") (pintype "passive"))
      (node (ref "AVR") (pin "22") (pinfunction "22_22") (pintype "bidirectional"))
    )
    (net (code "41") (name "Net-(23-P)") (class "Default")
      (node (ref "23") (pin "1") (pinfunction "P_1") (pintype "passive"))
      (node (ref "AVR") (pin "23") (pinfunction "23_23") (pintype "bidirectional"))
    )
    (net (code "42") (name "Net-(24-P)") (class "Default")
      (node (ref "24") (pin "1") (pinfunction "P_1") (pintype "passive"))
      (node (ref "AVR") (pin "24") (pinfunction "24_24") (pintype "bidirectional"))
    )
    (net (code "43") (name "Net-(25-P)") (class "Default")
      (node (ref "25") (pin "1") (pinfunction "P_1") (pintype "passive"))
      (node (ref "AVR") (pin "25") (pinfunction "25_25") (pintype "bidirectional"))
    )
    (net (code "44") (name "Net-(26-P)") (class "Default")
      (node (ref "26") (pin "1") (pinfunction "P_1") (pintype "passive"))
      (node (ref "AVR") (pin "26") (pinfunction "26_26") (pintype "bidirectional"))
    )
    (net (code "45") (name "Net-(27-P)") (class "Default")
      (node (ref "27") (pin "1") (pinfunction "P_1") (pintype "passive"))
      (node (ref "AVR") (pin "27") (pinfunction "27_27") (pintype "bidirectional"))
    )
    (net (code "46") (name "Net-(28-P)") (class "Default")
      (node (ref "28") (pin "1") (pinfunction "P_1") (pintype "passive"))
      (node (ref "AVR") (pin "28") (pinfunction "28_28") (pintype "bidirectional"))
    )
    (net (code "47") (name "Net-(29-P)") (class "Default")
      (node (ref "29") (pin "1") (pinfunction "P_1") (pintype "passive"))
      (node (ref "AVR") (pin "29") (pinfunction "29_29") (pintype "bidirectional"))
    )
    (net (code "48") (name "Net-(30-P)") (class "Default")
      (node (ref "30") (pin "1") (pinfunction "P_1") (pintype "passive"))
      (node (ref "AVR") (pin "30") (pinfunction "30_30") (pintype "bidirectional"))
    )
    (net (code "49") (name "Net-(31-P)") (class "Default")
      (node (ref "31") (pin "1") (pinfunction "P_1") (pintype "passive"))
      (node (ref "AVR") (pin "31") (pinfunction "31_31") (pintype "bidirectional"))
    )
    (net (code "50") (name "Net-(32-P)") (class "Default")
      (node (ref "32") (pin "1") (pinfunction "P_1") (pintype "passive"))
      (node (ref "AVR") (pin "32") (pinfunction "32_32") (pintype "bidirectional"))
    )
    (net (code "51") (name "Net-(33-P)") (class "Default")
      (node (ref "33") (pin "1") (pinfunction "P_1") (pintype "passive"))
      (node (ref "AVR") (pin "33") (pinfunction "33_33") (pintype "bidirectional"))
    )
    (net (code "52") (name "Net-(34-P)") (class "Default")
      (node (ref "34") (pin "1") (pinfunction "P_1") (pintype "passive"))
      (node (ref "AVR") (pin "34") (pinfunction "34_34") (pintype "bidirectional"))
    )
    (net (code "53") (name "Net-(35-P)") (class "Default")
      (node (ref "35") (pin "1") (pinfunction "P_1") (pintype "passive"))
      (node (ref "AVR") (pin "35") (pinfunction "35_35") (pintype "bidirectional"))
    )
    (net (code "54") (name "Net-(36-P)") (class "Default")
      (node (ref "36") (pin "1") (pinfunction "P_1") (pintype "passive"))
      (node (ref "AVR") (pin "36") (pinfunction "36_36") (pintype "bidirectional"))
    )
    (net (code "55") (name "Net-(37-P)") (class "Default")
      (node (ref "37") (pin "1") (pinfunction "P_1") (pintype "passive"))
      (node (ref "AVR") (pin "37") (pinfunction "37_37") (pintype "bidirectional"))
    )
    (net (code "56") (name "Net-(38-P)") (class "Default")
      (node (ref "38") (pin "1") (pinfunction "P_1") (pintype "passive"))
      (node (ref "AVR") (pin "38") (pinfunction "38_38") (pintype "bidirectional"))
    )
    (net (code "57") (name "Net-(39-P)") (class "Default")
      (node (ref "39") (pin "1") (pinfunction "P_1") (pintype "passive"))
      (node (ref "AVR") (pin "39") (pinfunction "39_39") (pintype "bidirectional"))
    )
    (net (code "58") (name "Net-(40-P)") (class "Default")
      (node (ref "40") (pin "1") (pinfunction "P_1") (pintype "passive"))
      (node (ref "AVR") (pin "40") (pinfunction "40_40") (pintype "bidirectional"))
    )
    (net (code "59") (name "Net-(41-P)") (class "Default")
      (node (ref "41") (pin "1") (pinfunction "P_1") (pintype "passive"))
      (node (ref "AVR") (pin "41") (pinfunction "41_41") (pintype "bidirectional"))
    )
    (net (code "60") (name "Net-(42-P)") (class "Default")
      (node (ref "42") (pin "1") (pinfunction "P_1") (pintype "passive"))
      (node (ref "AVR") (pin "42") (pinfunction "42_42") (pintype "bidirectional"))
    )
    (net (code "61") (name "Net-(43-P)") (class "Default")
      (node (ref "43") (pin "1") (pinfunction "P_1") (pintype "passive"))
      (node (ref "AVR") (pin "43") (pinfunction "43_43") (pintype "bidirectional"))
    )
    (net (code "62") (name "Net-(44-P)") (class "Default")
      (node (ref "44") (pin "1") (pinfunction "P_1") (pintype "passive"))
      (node (ref "AVR") (pin "44") (pinfunction "PWM/44_44") (pintype "bidirectional"))
    )
    (net (code "63") (name "Net-(45-P)") (class "Default")
      (node (ref "45") (pin "1") (pinfunction "P_1") (pintype "passive"))
      (node (ref "AVR") (pin "45") (pinfunction "PWM/45_45") (pintype "bidirectional"))
    )
    (net (code "64") (name "Net-(46-P)") (class "Default")
      (node (ref "46") (pin "1") (pinfunction "P_1") (pintype "passive"))
      (node (ref "AVR") (pin "46") (pinfunction "PWM/46_46") (pintype "bidirectional"))
    )
    (net (code "65") (name "Net-(47-P)") (class "Default")
      (node (ref "47") (pin "1") (pinfunction "P_1") (pintype "passive"))
      (node (ref "AVR") (pin "47") (pinfunction "47_47") (pintype "bidirectional"))
    )
    (net (code "66") (name "Net-(48-P)") (class "Default")
      (node (ref "48") (pin "1") (pinfunction "P_1") (pintype "passive"))
      (node (ref "AVR") (pin "48") (pinfunction "48_48") (pintype "bidirectional"))
    )
    (net (code "67") (name "Net-(49-P)") (class "Default")
      (node (ref "49") (pin "1") (pinfunction "P_1") (pintype "passive"))
      (node (ref "AVR") (pin "49") (pinfunction "49_49") (pintype "bidirectional"))
    )
    (net (code "68") (name "Net-(53-P)") (class "Default")
      (node (ref "53") (pin "1") (pinfunction "P_1") (pintype "passive"))
      (node (ref "AVR") (pin "53") (pinfunction "SS/53_53") (pintype "bidirectional"))
    )
    (net (code "69") (name "Net-(A0-P)") (class "Default")
      (node (ref "A0") (pin "1") (pinfunction "P_1") (pintype "passive"))
      (node (ref "AVR") (pin "AIN0") (pinfunction "AIN0_AIN0") (pintype "bidirectional"))
    )
    (net (code "70") (name "Net-(A1-P)") (class "Default")
      (node (ref "A1") (pin "1") (pinfunction "P_1") (pintype "passive"))
      (node (ref "AVR") (pin "AIN1") (pinfunction "AIN1_AIN1") (pintype "bidirectional"))
    )
    (net (code "71") (name "Net-(A2-P)") (class "Default")
      (node (ref "A2") (pin "1") (pinfunction "P_1") (pintype "passive"))
      (node (ref "AVR") (pin "AIN2") (pinfunction "AIN2_AIN2") (pintype "bidirectional"))
    )
    (net (code "72") (name "Net-(A3-P)") (class "Default")
      (node (ref "A3") (pin "1") (pinfunction "P_1") (pintype "passive"))
      (node (ref "AVR") (pin "AIN3") (pinfunction "AIN3_AIN3") (pintype "bidirectional"))
    )
    (net (code "73") (name "Net-(A6-P)") (class "Default")
      (node (ref "A6") (pin "1") (pinfunction "P_1") (pintype "passive"))
      (node (ref "AVR") (pin "AIN6") (pinfunction "AIN6_AIN6") (pintype "bidirectional"))
    )
    (net (code "74") (name "Net-(A7-P)") (class "Default")
      (node (ref "A7") (pin "1") (pinfunction "P_1") (pintype "passive"))
      (node (ref "AVR") (pin "AIN7") (pinfunction "AIN7_AIN7") (pintype "bidirectional"))
    )
    (net (code "75") (name "Net-(A8-P)") (class "Default")
      (node (ref "A8") (pin "1") (pinfunction "P_1") (pintype "passive"))
      (node (ref "AVR") (pin "AIN8") (pinfunction "AIN8_AIN8") (pintype "bidirectional"))
    )
    (net (code "76") (name "Net-(A9-P)") (class "Default")
      (node (ref "A9") (pin "1") (pinfunction "P_1") (pintype "passive"))
      (node (ref "AVR") (pin "AIN9") (pinfunction "AIN9_AIN9") (pintype "bidirectional"))
    )
    (net (code "77") (name "Net-(A10-P)") (class "Default")
      (node (ref "A10") (pin "1") (pinfunction "P_1") (pintype "passive"))
      (node (ref "AVR") (pin "AIN10") (pinfunction "AIN10_AIN10") (pintype "bidirectional"))
    )
    (net (code "78") (name "Net-(A11-P)") (class "Default")
      (node (ref "A11") (pin "1") (pinfunction "P_1") (pintype "passive"))
      (node (ref "AVR") (pin "AIN11") (pinfunction "AIN11_AIN11") (pintype "bidirectional"))
    )
    (net (code "79") (name "Net-(A12-P)") (class "Default")
      (node (ref "A12") (pin "1") (pinfunction "P_1") (pintype "passive"))
      (node (ref "AVR") (pin "AIN12") (pinfunction "AIN12_AIN12") (pintype "bidirectional"))
    )
    (net (code "80") (name "Net-(A13-P)") (class "Default")
      (node (ref "A13") (pin "1") (pinfunction "P_1") (pintype "passive"))
      (node (ref "AVR") (pin "AIN13") (pinfunction "AIN13_AIN13") (pintype "bidirectional"))
    )
    (net (code "81") (name "Net-(A14-P)") (class "Default")
      (node (ref "A14") (pin "1") (pinfunction "P_1") (pintype "passive"))
      (node (ref "AVR") (pin "AIN14") (pinfunction "AIN14_AIN14") (pintype "bidirectional"))
    )
    (net (code "82") (name "Net-(A15-P)") (class "Default")
      (node (ref "A15") (pin "1") (pinfunction "P_1") (pintype "passive"))
      (node (ref "AVR") (pin "AIN15") (pinfunction "AIN15_AIN15") (pintype "bidirectional"))
    )
    (net (code "83") (name "Net-(ADS_BUSY-Pad1)") (class "Default")
      (node (ref "ADS_BUSY") (pin "1") (pinfunction "1_1") (pintype "passive"))
      (node (ref "CON1") (pin "12") (pinfunction "12_12") (pintype "passive"))
    )
    (net (code "84") (name "Net-(ADS_IRQ-Pad1)") (class "Default")
      (node (ref "ADS_IRQ") (pin "1") (pinfunction "1_1") (pintype "passive"))
      (node (ref "CON1") (pin "13") (pinfunction "13_13") (pintype "passive"))
    )
    (net (code "85") (name "Net-(AREF-P)") (class "Default")
      (node (ref "AREF") (pin "1") (pinfunction "P_1") (pintype "passive"))
      (node (ref "AVR") (pin "AREF") (pinfunction "AREF_AREF") (pintype "power_in"))
    )
    (net (code "86") (name "Net-(AVR-RESET)") (class "Default")
      (node (ref "AVR") (pin "RST") (pinfunction "RESET_RST") (pintype "bidirectional"))
      (node (ref "RST") (pin "1") (pinfunction "P_1") (pintype "passive"))
    )
    (net (code "87") (name "Net-(I1-P)") (class "Default")
      (node (ref "I1") (pin "1") (pinfunction "P_1") (pintype "passive"))
      (node (ref "IC1") (pin "8") (pinfunction "A4_8") (pintype "input"))
      (node (ref "R4") (pin "2") (pinfunction "2_2") (pintype "passive"))
    )
    (net (code "88") (name "Net-(I2-P)") (class "Default")
      (node (ref "I2") (pin "1") (pinfunction "P_1") (pintype "passive"))
      (node (ref "IC1") (pin "11") (pinfunction "A1_11") (pintype "input"))
      (node (ref "R5") (pin "2") (pinfunction "2_2") (pintype "passive"))
    )
    (net (code "89") (name "Net-(I3-P)") (class "Default")
      (node (ref "I3") (pin "1") (pinfunction "P_1") (pintype "passive"))
      (node (ref "IC1") (pin "13") (pinfunction "A2_13") (pintype "input"))
      (node (ref "R6") (pin "2") (pinfunction "2_2") (pintype "passive"))
    )
    (net (code "90") (name "Net-(I4-P)") (class "Default")
      (node (ref "I4") (pin "1") (pinfunction "P_1") (pintype "passive"))
      (node (ref "IC1") (pin "15") (pinfunction "A3_15") (pintype "input"))
      (node (ref "R7") (pin "2") (pinfunction "2_2") (pintype "passive"))
    )
    (net (code "91") (name "Net-(IC1A-Y4)") (class "Default")
      (node (ref "IC1") (pin "12") (pinfunction "Y4_12") (pintype "tri_state"))
      (node (ref "O1") (pin "1") (pinfunction "P_1") (pintype "passive"))
    )
    (net (code "92") (name "Net-(IC1B-Y1)") (class "Default")
      (node (ref "IC1") (pin "9") (pinfunction "Y1_9") (pintype "tri_state"))
      (node (ref "O2") (pin "1") (pinfunction "P_1") (pintype "passive"))
    )
    (net (code "93") (name "Net-(IC1B-Y2)") (class "Default")
      (node (ref "IC1") (pin "7") (pinfunction "Y2_7") (pintype "tri_state"))
      (node (ref "O3") (pin "1") (pinfunction "P_1") (pintype "passive"))
    )
    (net (code "94") (name "Net-(IC1B-Y3)") (class "Default")
      (node (ref "IC1") (pin "5") (pinfunction "Y3_5") (pintype "tri_state"))
      (node (ref "O4") (pin "1") (pinfunction "P_1") (pintype "passive"))
    )
    (net (code "95") (name "Net-(IC2-VBAT)") (class "Default")
      (node (ref "BAT") (pin "VCC1") (pinfunction "VCC_VCC1") (pintype "power_in"))
      (node (ref "BAT") (pin "VCC2") (pinfunction "VCC_VCC2") (pintype "power_in"))
      (node (ref "IC2") (pin "3") (pinfunction "VBAT_3") (pintype "power_in"))
    )
    (net (code "96") (name "Net-(IC2-X1)") (class "Default")
      (node (ref "IC2") (pin "1") (pinfunction "X1_1") (pintype "bidirectional"))
      (node (ref "Q1") (pin "2") (pinfunction "2_2") (pintype "passive"))
    )
    (net (code "97") (name "Net-(IC2-X2)") (class "Default")
      (node (ref "IC2") (pin "2") (pinfunction "X2_2") (pintype "bidirectional"))
      (node (ref "Q1") (pin "1") (pinfunction "1_1") (pintype "passive"))
    )
    (net (code "98") (name "Net-(R1-Pad2)") (class "Default")
      (node (ref "R1") (pin "2") (pinfunction "2_2") (pintype "passive"))
      (node (ref "X5") (pin "8") (pinfunction "8_8") (pintype "bidirectional"))
    )
    (net (code "99") (name "Net-(R2-Pad2)") (class "Default")
      (node (ref "R2") (pin "2") (pinfunction "2_2") (pintype "passive"))
      (node (ref "X5") (pin "1") (pinfunction "1_1") (pintype "bidirectional"))
    )
    (net (code "100") (name "Net-(U1-VO)") (class "Default")
      (node (ref "3V3") (pin "1") (pinfunction "1_1") (pintype "passive"))
      (node (ref "C2") (pin "1") (pinfunction "1_1") (pintype "passive"))
      (node (ref "U1") (pin "1") (pinfunction "VO_1") (pintype "passive"))
    )
    (net (code "101") (name "Net-(VIN-P)") (class "Default")
      (node (ref "AVR") (pin "VIN") (pinfunction "VIN_VIN") (pintype "power_in"))
      (node (ref "VIN") (pin "1") (pinfunction "P_1") (pintype "passive"))
    )
    (net (code "102") (name "Net-(X5-SW1)") (class "Default")
      (node (ref "SD_DETECT") (pin "1") (pinfunction "1_1") (pintype "passive"))
      (node (ref "X5") (pin "K1") (pinfunction "SW1_K1") (pintype "bidirectional"))
    )
    (net (code "103") (name "unconnected-(IC1B-Y4-Pad3)") (class "Default")
      (node (ref "IC1") (pin "3") (pinfunction "Y4_3") (pintype "tri_state"))
    )
  )
)
